# unifying_sht2.net
KiCad netlist of a schematic drawn in Altium Designer
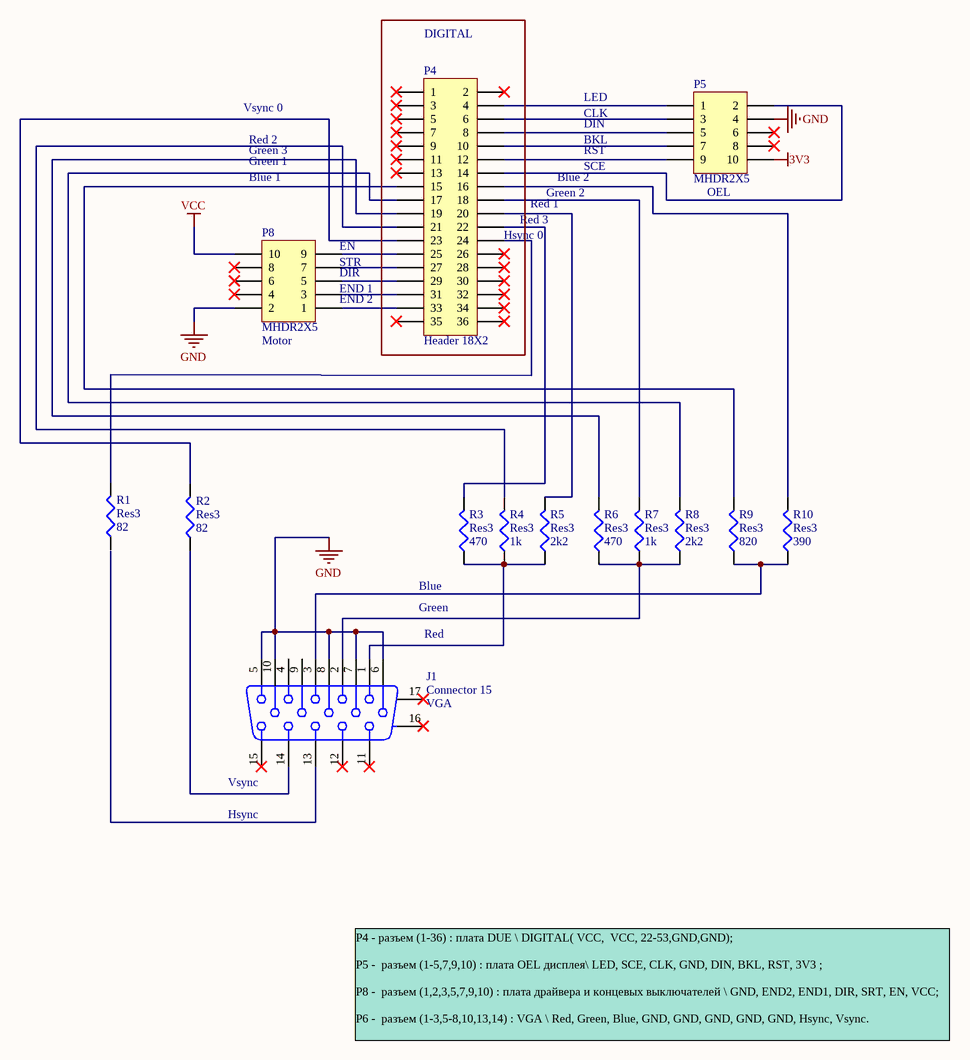
[diagram p0: unifying_sht2.SchDoc]

(export (version "E")
  (design (tool "Eeschema 10.0.6"))
  (components
    (comp (ref "J1")
      (value "Connector 15")
      (footprint "050DSUB0.762-4H15")
      (description "Receptacle Assembly, 15-Pin, Sim Line Connector")
      (fields (field (name "ALTIUM_UNNAMED_1") "VGA") (field (name "PUBLISHER") "Altium Limited"))
      (libsource (lib "Miscellaneous Connectors") (part "Connector 15"))
    )
    (comp (ref "P4")
      (value "Header 18X2")
      (footprint "HDR2X18")
      (description "Header, 18-Pin, Dual row")
      (fields (field (name "PUBLISHER") "Altium Limited"))
      (libsource (lib "Miscellaneous Connectors") (part "Header 18X2"))
    )
    (comp (ref "P5")
      (value "MHDR2X5")
      (footprint "MHDR2X5")
      (description "Header, 5-Pin, Dual row")
      (fields (field (name "ALTIUM_UNNAMED_1") "OEL") (field (name "PUBLISHER") "Altium Limited"))
      (libsource (lib "") (part "MHDR2X5_1"))
    )
    (comp (ref "P8")
      (value "MHDR2X5")
      (footprint "MHDR2X5")
      (description "Header, 5-Pin, Dual row")
      (fields (field (name "ALTIUM_UNNAMED_1") "Motor") (field (name "PUBLISHER") "Altium Limited"))
      (libsource (lib "Miscellaneous Connectors") (part "MHDR2X5"))
    )
    (comp (ref "R1")
      (value "Res3")
      (footprint "J1-0603")
      (description "Resistor")
      (fields (field (name "ALTIUM_VALUE") "82") (field (name "PUBLISHER") "Altium Limited"))
      (libsource (lib "Miscellaneous Devices") (part "Res3"))
    )
    (comp (ref "R2")
      (value "Res3")
      (footprint "J1-0603")
      (description "Resistor")
      (fields (field (name "ALTIUM_VALUE") "82") (field (name "PUBLISHER") "Altium Limited"))
      (libsource (lib "Miscellaneous Devices") (part "Res3"))
    )
    (comp (ref "R3")
      (value "Res3")
      (footprint "J1-0603")
      (description "Resistor")
      (fields (field (name "ALTIUM_VALUE") "470") (field (name "PUBLISHER") "Altium Limited"))
      (libsource (lib "Miscellaneous Devices") (part "Res3"))
    )
    (comp (ref "R4")
      (value "Res3")
      (footprint "J1-0603")
      (description "Resistor")
      (fields (field (name "ALTIUM_VALUE") "1k") (field (name "PUBLISHER") "Altium Limited"))
      (libsource (lib "Miscellaneous Devices") (part "Res3"))
    )
    (comp (ref "R5")
      (value "Res3")
      (footprint "J1-0603")
      (description "Resistor")
      (fields (field (name "ALTIUM_VALUE") "2k2") (field (name "PUBLISHER") "Altium Limited"))
      (libsource (lib "Miscellaneous Devices") (part "Res3"))
    )
    (comp (ref "R6")
      (value "Res3")
      (footprint "J1-0603")
      (description "Resistor")
      (fields (field (name "ALTIUM_VALUE") "470") (field (name "PUBLISHER") "Altium Limited"))
      (libsource (lib "Miscellaneous Devices") (part "Res3"))
    )
    (comp (ref "R7")
      (value "Res3")
      (footprint "J1-0603")
      (description "Resistor")
      (fields (field (name "ALTIUM_VALUE") "1k") (field (name "PUBLISHER") "Altium Limited"))
      (libsource (lib "Miscellaneous Devices") (part "Res3"))
    )
    (comp (ref "R8")
      (value "Res3")
      (footprint "J1-0603")
      (description "Resistor")
      (fields (field (name "ALTIUM_VALUE") "2k2") (field (name "PUBLISHER") "Altium Limited"))
      (libsource (lib "Miscellaneous Devices") (part "Res3"))
    )
    (comp (ref "R9")
      (value "Res3")
      (footprint "J1-0603")
      (description "Resistor")
      (fields (field (name "ALTIUM_VALUE") "820") (field (name "PUBLISHER") "Altium Limited"))
      (libsource (lib "Miscellaneous Devices") (part "Res3"))
    )
    (comp (ref "R10")
      (value "Res3")
      (footprint "J1-0603")
      (description "Resistor")
      (fields (field (name "ALTIUM_VALUE") "390") (field (name "PUBLISHER") "Altium Limited"))
      (libsource (lib "Miscellaneous Devices") (part "Res3"))
    )
  )
  (nets
    (net (code "1") (name "3V3") (class "Default")
      (node (ref "P5") (pin "10") (pinfunction "10_10") (pintype "passive"))
    )
    (net (code "2") (name "GND") (class "Default")
      (node (ref "J1") (pin "10") (pinfunction "10_10") (pintype "passive"))
      (node (ref "J1") (pin "5") (pinfunction "5_5") (pintype "passive"))
      (node (ref "J1") (pin "6") (pinfunction "6_6") (pintype "passive"))
      (node (ref "J1") (pin "7") (pinfunction "7_7") (pintype "passive"))
      (node (ref "J1") (pin "8") (pinfunction "8_8") (pintype "passive"))
      (node (ref "P5") (pin "4") (pinfunction "4_4") (pintype "passive"))
      (node (ref "P8") (pin "2") (pinfunction "2_2") (pintype "passive"))
    )
    (net (code "3") (name "Net-(J1-Pad1)") (class "Default")
      (node (ref "J1") (pin "1") (pinfunction "1_1") (pintype "passive"))
      (node (ref "R3") (pin "1") (pinfunction "1_1") (pintype "passive"))
      (node (ref "R4") (pin "1") (pinfunction "1_1") (pintype "passive"))
      (node (ref "R5") (pin "1") (pinfunction "1_1") (pintype "passive"))
    )
    (net (code "4") (name "Net-(J1-Pad2)") (class "Default")
      (node (ref "J1") (pin "2") (pinfunction "2_2") (pintype "passive"))
      (node (ref "R6") (pin "1") (pinfunction "1_1") (pintype "passive"))
      (node (ref "R7") (pin "1") (pinfunction "1_1") (pintype "passive"))
      (node (ref "R8") (pin "1") (pinfunction "1_1") (pintype "passive"))
    )
    (net (code "5") (name "Net-(J1-Pad3)") (class "Default")
      (node (ref "J1") (pin "3") (pinfunction "3_3") (pintype "passive"))
      (node (ref "R10") (pin "1") (pinfunction "1_1") (pintype "passive"))
      (node (ref "R9") (pin "1") (pinfunction "1_1") (pintype "passive"))
    )
    (net (code "6") (name "Net-(J1-Pad14)") (class "Default")
      (node (ref "J1") (pin "14") (pinfunction "14_14") (pintype "passive"))
      (node (ref "R2") (pin "1") (pinfunction "1_1") (pintype "passive"))
    )
    (net (code "7") (name "Net-(P4-Pad4)") (class "Default")
      (node (ref "P4") (pin "4") (pinfunction "4_4") (pintype "passive"))
      (node (ref "P5") (pin "1") (pinfunction "1_1") (pintype "passive"))
    )
    (net (code "8") (name "Net-(P4-Pad6)") (class "Default")
      (node (ref "P4") (pin "6") (pinfunction "6_6") (pintype "passive"))
      (node (ref "P5") (pin "3") (pinfunction "3_3") (pintype "passive"))
    )
    (net (code "9") (name "Net-(P4-Pad8)") (class "Default")
      (node (ref "P4") (pin "8") (pinfunction "8_8") (pintype "passive"))
      (node (ref "P5") (pin "5") (pinfunction "5_5") (pintype "passive"))
    )
    (net (code "10") (name "Net-(P4-Pad10)") (class "Default")
      (node (ref "P4") (pin "10") (pinfunction "10_10") (pintype "passive"))
      (node (ref "P5") (pin "7") (pinfunction "7_7") (pintype "passive"))
    )
    (net (code "11") (name "Net-(P4-Pad12)") (class "Default")
      (node (ref "P4") (pin "12") (pinfunction "12_12") (pintype "passive"))
      (node (ref "P5") (pin "9") (pinfunction "9_9") (pintype "passive"))
    )
    (net (code "12") (name "Net-(P4-Pad14)") (class "Default")
      (node (ref "P4") (pin "14") (pinfunction "14_14") (pintype "passive"))
      (node (ref "P5") (pin "2") (pinfunction "2_2") (pintype "passive"))
    )
    (net (code "13") (name "Net-(P4-Pad15)") (class "Default")
      (node (ref "P4") (pin "15") (pinfunction "15_15") (pintype "passive"))
      (node (ref "R9") (pin "2") (pinfunction "2_2") (pintype "passive"))
    )
    (net (code "14") (name "Net-(P4-Pad16)") (class "Default")
      (node (ref "P4") (pin "16") (pinfunction "16_16") (pintype "passive"))
      (node (ref "R10") (pin "2") (pinfunction "2_2") (pintype "passive"))
    )
    (net (code "15") (name "Net-(P4-Pad17)") (class "Default")
      (node (ref "P4") (pin "17") (pinfunction "17_17") (pintype "passive"))
      (node (ref "R8") (pin "2") (pinfunction "2_2") (pintype "passive"))
    )
    (net (code "16") (name "Net-(P4-Pad18)") (class "Default")
      (node (ref "P4") (pin "18") (pinfunction "18_18") (pintype "passive"))
      (node (ref "R7") (pin "2") (pinfunction "2_2") (pintype "passive"))
    )
    (net (code "17") (name "Net-(P4-Pad19)") (class "Default")
      (node (ref "P4") (pin "19") (pinfunction "19_19") (pintype "passive"))
      (node (ref "R6") (pin "2") (pinfunction "2_2") (pintype "passive"))
    )
    (net (code "18") (name "Net-(P4-Pad20)") (class "Default")
      (node (ref "P4") (pin "20") (pinfunction "20_20") (pintype "passive"))
      (node (ref "R5") (pin "2") (pinfunction "2_2") (pintype "passive"))
    )
    (net (code "19") (name "Net-(P4-Pad21)") (class "Default")
      (node (ref "P4") (pin "21") (pinfunction "21_21") (pintype "passive"))
      (node (ref "R4") (pin "2") (pinfunction "2_2") (pintype "passive"))
    )
    (net (code "20") (name "Net-(P4-Pad22)") (class "Default")
      (node (ref "P4") (pin "22") (pinfunction "22_22") (pintype "passive"))
      (node (ref "R3") (pin "2") (pinfunction "2_2") (pintype "passive"))
    )
    (net (code "21") (name "Net-(P4-Pad23)") (class "Default")
      (node (ref "P4") (pin "23") (pinfunction "23_23") (pintype "passive"))
      (node (ref "R2") (pin "2") (pinfunction "2_2") (pintype "passive"))
    )
    (net (code "22") (name "Net-(P4-Pad24)") (class "Default")
      (node (ref "P4") (pin "24") (pinfunction "24_24") (pintype "passive"))
      (node (ref "R1") (pin "2") (pinfunction "2_2") (pintype "passive"))
    )
    (net (code "23") (name "Net-(P4-Pad25)") (class "Default")
      (node (ref "P4") (pin "25") (pinfunction "25_25") (pintype "passive"))
      (node (ref "P8") (pin "9") (pinfunction "9_9") (pintype "passive"))
    )
    (net (code "24") (name "Net-(P4-Pad27)") (class "Default")
      (node (ref "P4") (pin "27") (pinfunction "27_27") (pintype "passive"))
      (node (ref "P8") (pin "7") (pinfunction "7_7") (pintype "passive"))
    )
    (net (code "25") (name "Net-(P4-Pad29)") (class "Default")
      (node (ref "P4") (pin "29") (pinfunction "29_29") (pintype "passive"))
      (node (ref "P8") (pin "5") (pinfunction "5_5") (pintype "passive"))
    )
    (net (code "26") (name "Net-(P4-Pad31)") (class "Default")
      (node (ref "P4") (pin "31") (pinfunction "31_31") (pintype "passive"))
      (node (ref "P8") (pin "3") (pinfunction "3_3") (pintype "passive"))
    )
    (net (code "27") (name "Net-(P4-Pad33)") (class "Default")
      (node (ref "P4") (pin "33") (pinfunction "33_33") (pintype "passive"))
      (node (ref "P8") (pin "1") (pinfunction "1_1") (pintype "passive"))
    )
    (net (code "28") (name "VCC") (class "Default")
      (node (ref "P8") (pin "10") (pinfunction "10_10") (pintype "passive"))
    )
    (net (code "29") (name "unconnected-(J1-MH1-Pad16)") (class "Default")
      (node (ref "J1") (pin "16") (pinfunction "MH1_16") (pintype "passive+no_connect"))
    )
    (net (code "30") (name "unconnected-(J1-MH2-Pad17)") (class "Default")
      (node (ref "J1") (pin "17") (pinfunction "MH2_17") (pintype "passive+no_connect"))
    )
    (net (code "31") (name "unconnected-(J1-Pad4)") (class "Default")
      (node (ref "J1") (pin "4") (pinfunction "4_4") (pintype "passive"))
    )
    (net (code "32") (name "unconnected-(J1-Pad9)") (class "Default")
      (node (ref "J1") (pin "9") (pinfunction "9_9") (pintype "passive"))
    )
    (net (code "33") (name "unconnected-(J1-Pad11)") (class "Default")
      (node (ref "J1") (pin "11") (pinfunction "11_11") (pintype "passive+no_connect"))
    )
    (net (code "34") (name "unconnected-(J1-Pad12)") (class "Default")
      (node (ref "J1") (pin "12") (pinfunction "12_12") (pintype "passive+no_connect"))
    )
    (net (code "35") (name "unconnected-(J1-Pad13)") (class "Default")
      (node (ref "J1") (pin "13") (pinfunction "13_13") (pintype "passive"))
    )
    (net (code "36") (name "unconnected-(J1-Pad15)") (class "Default")
      (node (ref "J1") (pin "15") (pinfunction "15_15") (pintype "passive+no_connect"))
    )
    (net (code "37") (name "unconnected-(P4-Pad1)") (class "Default")
      (node (ref "P4") (pin "1") (pinfunction "1_1") (pintype "passive+no_connect"))
    )
    (net (code "38") (name "unconnected-(P4-Pad2)") (class "Default")
      (node (ref "P4") (pin "2") (pinfunction "2_2") (pintype "passive+no_connect"))
    )
    (net (code "39") (name "unconnected-(P4-Pad3)") (class "Default")
      (node (ref "P4") (pin "3") (pinfunction "3_3") (pintype "passive+no_connect"))
    )
    (net (code "40") (name "unconnected-(P4-Pad5)") (class "Default")
      (node (ref "P4") (pin "5") (pinfunction "5_5") (pintype "passive+no_connect"))
    )
    (net (code "41") (name "unconnected-(P4-Pad7)") (class "Default")
      (node (ref "P4") (pin "7") (pinfunction "7_7") (pintype "passive+no_connect"))
    )
    (net (code "42") (name "unconnected-(P4-Pad9)") (class "Default")
      (node (ref "P4") (pin "9") (pinfunction "9_9") (pintype "passive+no_connect"))
    )
    (net (code "43") (name "unconnected-(P4-Pad11)") (class "Default")
      (node (ref "P4") (pin "11") (pinfunction "11_11") (pintype "passive+no_connect"))
    )
    (net (code "44") (name "unconnected-(P4-Pad13)") (class "Default")
      (node (ref "P4") (pin "13") (pinfunction "13_13") (pintype "passive+no_connect"))
    )
    (net (code "45") (name "unconnected-(P4-Pad26)") (class "Default")
      (node (ref "P4") (pin "26") (pinfunction "26_26") (pintype "passive+no_connect"))
    )
    (net (code "46") (name "unconnected-(P4-Pad28)") (class "Default")
      (node (ref "P4") (pin "28") (pinfunction "28_28") (pintype "passive+no_connect"))
    )
    (net (code "47") (name "unconnected-(P4-Pad30)") (class "Default")
      (node (ref "P4") (pin "30") (pinfunction "30_30") (pintype "passive+no_connect"))
    )
    (net (code "48") (name "unconnected-(P4-Pad32)") (class "Default")
      (node (ref "P4") (pin "32") (pinfunction "32_32") (pintype "passive+no_connect"))
    )
    (net (code "49") (name "unconnected-(P4-Pad34)") (class "Default")
      (node (ref "P4") (pin "34") (pinfunction "34_34") (pintype "passive+no_connect"))
    )
    (net (code "50") (name "unconnected-(P4-Pad35)") (class "Default")
      (node (ref "P4") (pin "35") (pinfunction "35_35") (pintype "passive+no_connect"))
    )
    (net (code "51") (name "unconnected-(P4-Pad36)") (class "Default")
      (node (ref "P4") (pin "36") (pinfunction "36_36") (pintype "passive+no_connect"))
    )
    (net (code "52") (name "unconnected-(P5-Pad6)") (class "Default")
      (node (ref "P5") (pin "6") (pinfunction "6_6") (pintype "passive+no_connect"))
    )
    (net (code "53") (name "unconnected-(P5-Pad8)") (class "Default")
      (node (ref "P5") (pin "8") (pinfunction "8_8") (pintype "passive+no_connect"))
    )
    (net (code "54") (name "unconnected-(P8-Pad4)") (class "Default")
      (node (ref "P8") (pin "4") (pinfunction "4_4") (pintype "passive+no_connect"))
    )
    (net (code "55") (name "unconnected-(P8-Pad6)") (class "Default")
      (node (ref "P8") (pin "6") (pinfunction "6_6") (pintype "passive+no_connect"))
    )
    (net (code "56") (name "unconnected-(P8-Pad8)") (class "Default")
      (node (ref "P8") (pin "8") (pinfunction "8_8") (pintype "passive+no_connect"))
    )
    (net (code "57") (name "unconnected-(R1-Pad1)") (class "Default")
      (node (ref "R1") (pin "1") (pinfunction "1_1") (pintype "passive"))
    )
  )
)
